# untitled.net
KiCad netlist of a schematic drawn in EAGLE
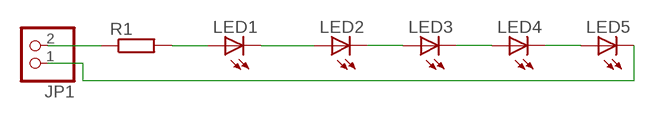
[diagram p0: schematic, sheet 1]

(export (version "E")
  (design (tool "Eeschema 10.0.6"))
  (components
    (comp (ref "JP1")
      (value "PINHD-1X2/90")
      (footprint "eagle-import:1X02_90")
      (libsource (lib "eagle-import") (part "PINHD-1X2/90"))
    )
    (comp (ref "LED1")
      (value "LED5MM")
      (footprint "eagle-import:LED5MM")
      (libsource (lib "eagle-import") (part "LED5MM"))
    )
    (comp (ref "LED2")
      (value "LED5MM")
      (footprint "eagle-import:LED5MM")
      (libsource (lib "eagle-import") (part "LED5MM"))
    )
    (comp (ref "LED3")
      (value "LED5MM")
      (footprint "eagle-import:LED5MM")
      (libsource (lib "eagle-import") (part "LED5MM"))
    )
    (comp (ref "LED4")
      (value "LED5MM")
      (footprint "eagle-import:LED5MM")
      (libsource (lib "eagle-import") (part "LED5MM"))
    )
    (comp (ref "LED5")
      (value "LED5MM")
      (footprint "eagle-import:LED5MM")
      (libsource (lib "eagle-import") (part "LED5MM"))
    )
    (comp (ref "R1")
      (value "R-EU_0204/2V")
      (footprint "eagle-import:0204V")
      (libsource (lib "eagle-import") (part "R-EU_0204/2V"))
    )
  )
  (nets
    (net (code "1") (name "Net-(JP1-Pad2)") (class "Default")
      (node (ref "JP1") (pin "2") (pinfunction "2_2") (pintype "passive"))
      (node (ref "R1") (pin "1") (pinfunction "1_1") (pintype "passive"))
    )
    (net (code "2") (name "Net-(LED1-C)") (class "Default")
      (node (ref "LED1") (pin "K") (pinfunction "C_K") (pintype "passive"))
      (node (ref "LED2") (pin "A") (pinfunction "A_A") (pintype "passive"))
    )
    (net (code "3") (name "Net-(LED1-PadA)") (class "Default")
      (node (ref "LED1") (pin "A") (pinfunction "A_A") (pintype "passive"))
      (node (ref "R1") (pin "2") (pinfunction "2_2") (pintype "passive"))
    )
    (net (code "4") (name "Net-(LED2-C)") (class "Default")
      (node (ref "LED2") (pin "K") (pinfunction "C_K") (pintype "passive"))
      (node (ref "LED3") (pin "A") (pinfunction "A_A") (pintype "passive"))
    )
    (net (code "5") (name "Net-(LED3-C)") (class "Default")
      (node (ref "LED3") (pin "K") (pinfunction "C_K") (pintype "passive"))
      (node (ref "LED4") (pin "A") (pinfunction "A_A") (pintype "passive"))
    )
    (net (code "6") (name "Net-(LED4-C)") (class "Default")
      (node (ref "LED4") (pin "K") (pinfunction "C_K") (pintype "passive"))
      (node (ref "LED5") (pin "A") (pinfunction "A_A") (pintype "passive"))
    )
    (net (code "7") (name "Net-(LED5-C)") (class "Default")
      (node (ref "JP1") (pin "1") (pinfunction "1_1") (pintype "passive"))
      (node (ref "LED5") (pin "K") (pinfunction "C_K") (pintype "passive"))
    )
  )
)
